# 42_PP1_NC.net
KiCad netlist of a schematic drawn in Altium Designer
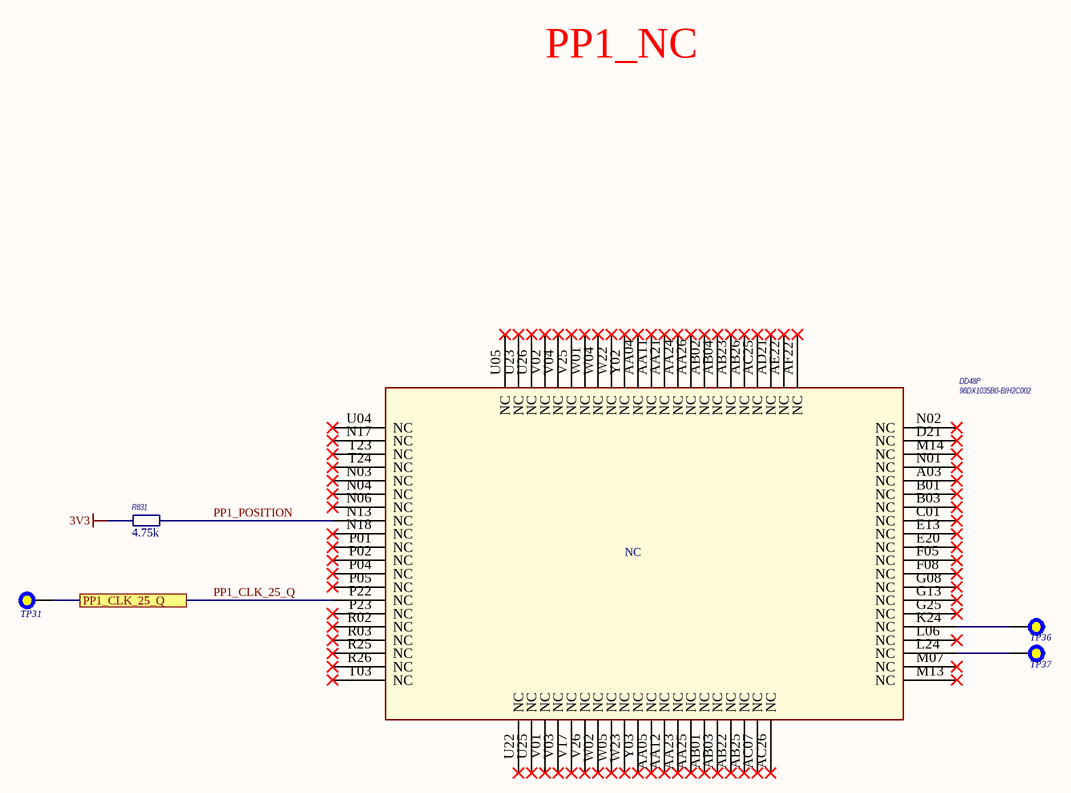
[diagram p0: 42_PP1_NC.SchDoc]

(export (version "E")
  (design (tool "Eeschema 10.0.6"))
  (components
    (comp (ref "DD48")
      (value "98DX1035B0-BIH2C002")
      (footprint "HSBGA617_27X27_1MM")
      (description "IC 24-PORT FE  4-PORT 2.5GE L2 ENTRY-LEVEL, CPU")
      (fields
        (field (name "CUSTOMER PART NUMBER") "Микросхема, 98DX1035B0-BIH2C002, IC 24-PORT FE 4-PORT 2.5GE L2 ENTRY-LEVEL, HSBGA617SBGA617")
        (field (name "MANUFACTURER") "Marvell Technology Group")
      )
      (libsource (lib "DIGITAL and ANALIG ICs") (part "98DX1035A1-BIH2C002"))
    )
    (comp (ref "R831")
      (value "ERJ-2RKF4751X")
      (footprint "R0402_IPC High Density")
      (description "R0402, 4.75k 1%")
      (fields
        (field (name "TOLERANCE") "±1%")
        (field (name "MANUFACTURER") "Panasonic")
        (field (name "RESISTANCE (OHMS)") "4.75k")
      )
      (libsource (lib "RESISTOR") (part "ERJ-2RKF4751X"))
    )
    (comp (ref "TP31")
      (value "Test Point 0.5mm pad")
      (footprint "Test Point 0.5mm")
      (libsource (lib "CONNECTORS") (part "Test Point 0.5mm pad"))
    )
    (comp (ref "TP36")
      (value "Test Point 0.5mm pad")
      (footprint "Test Point 0.5mm")
      (libsource (lib "CONNECTORS") (part "Test Point 0.5mm pad"))
    )
    (comp (ref "TP37")
      (value "Test Point 0.5mm pad")
      (footprint "Test Point 0.5mm")
      (libsource (lib "CONNECTORS") (part "Test Point 0.5mm pad"))
    )
  )
  (nets
    (net (code "1") (name "/PP1_CLK_25_Q") (class "Default")
      (node (ref "DD48") (pin "P22") (pinfunction "NC_P22") (pintype "power_in"))
      (node (ref "TP31") (pin "1") (pinfunction "1_1") (pintype "passive"))
    )
    (net (code "2") (name "/PP1_POSITION") (class "Default")
      (node (ref "DD48") (pin "N13") (pinfunction "NC_N13") (pintype "power_in"))
      (node (ref "R831") (pin "2") (pintype "passive"))
    )
    (net (code "3") (name "3V3") (class "Default") (node (ref "R831") (pin "1") (pintype "passive")))
    (net (code "4") (name "Net-(DD48P-NC-PadK24)") (class "Default")
      (node (ref "DD48") (pin "K24") (pinfunction "NC_K24") (pintype "power_in"))
      (node (ref "TP36") (pin "1") (pinfunction "1_1") (pintype "passive"))
    )
    (net (code "5") (name "Net-(DD48P-NC-PadL24)") (class "Default")
      (node (ref "DD48") (pin "L24") (pinfunction "NC_L24") (pintype "power_in"))
      (node (ref "TP37") (pin "1") (pinfunction "1_1") (pintype "passive"))
    )
    (net (code "6") (name "unconnected-(DD48P-NC-PadA03)") (class "Default")
      (node (ref "DD48") (pin "A03") (pinfunction "NC_A03") (pintype "power_in+no_connect"))
    )
    (net (code "7") (name "unconnected-(DD48P-NC-PadAA04)") (class "Default")
      (node (ref "DD48") (pin "AA04") (pinfunction "NC_AA04") (pintype "power_in+no_connect"))
    )
    (net (code "8") (name "unconnected-(DD48P-NC-PadAA05)") (class "Default")
      (node (ref "DD48") (pin "AA05") (pinfunction "NC_AA05") (pintype "power_in+no_connect"))
    )
    (net (code "9") (name "unconnected-(DD48P-NC-PadAA11)") (class "Default")
      (node (ref "DD48") (pin "AA11") (pinfunction "NC_AA11") (pintype "power_in+no_connect"))
    )
    (net (code "10") (name "unconnected-(DD48P-NC-PadAA12)") (class "Default")
      (node (ref "DD48") (pin "AA12") (pinfunction "NC_AA12") (pintype "power_in+no_connect"))
    )
    (net (code "11") (name "unconnected-(DD48P-NC-PadAA21)") (class "Default")
      (node (ref "DD48") (pin "AA21") (pinfunction "NC_AA21") (pintype "power_in+no_connect"))
    )
    (net (code "12") (name "unconnected-(DD48P-NC-PadAA23)") (class "Default")
      (node (ref "DD48") (pin "AA23") (pinfunction "NC_AA23") (pintype "power_in+no_connect"))
    )
    (net (code "13") (name "unconnected-(DD48P-NC-PadAA24)") (class "Default")
      (node (ref "DD48") (pin "AA24") (pinfunction "NC_AA24") (pintype "power_in+no_connect"))
    )
    (net (code "14") (name "unconnected-(DD48P-NC-PadAA25)") (class "Default")
      (node (ref "DD48") (pin "AA25") (pinfunction "NC_AA25") (pintype "power_in+no_connect"))
    )
    (net (code "15") (name "unconnected-(DD48P-NC-PadAA26)") (class "Default")
      (node (ref "DD48") (pin "AA26") (pinfunction "NC_AA26") (pintype "power_in+no_connect"))
    )
    (net (code "16") (name "unconnected-(DD48P-NC-PadAB01)") (class "Default")
      (node (ref "DD48") (pin "AB01") (pinfunction "NC_AB01") (pintype "power_in+no_connect"))
    )
    (net (code "17") (name "unconnected-(DD48P-NC-PadAB02)") (class "Default")
      (node (ref "DD48") (pin "AB02") (pinfunction "NC_AB02") (pintype "power_in+no_connect"))
    )
    (net (code "18") (name "unconnected-(DD48P-NC-PadAB03)") (class "Default")
      (node (ref "DD48") (pin "AB03") (pinfunction "NC_AB03") (pintype "power_in+no_connect"))
    )
    (net (code "19") (name "unconnected-(DD48P-NC-PadAB04)") (class "Default")
      (node (ref "DD48") (pin "AB04") (pinfunction "NC_AB04") (pintype "power_in+no_connect"))
    )
    (net (code "20") (name "unconnected-(DD48P-NC-PadAB22)") (class "Default")
      (node (ref "DD48") (pin "AB22") (pinfunction "NC_AB22") (pintype "power_in+no_connect"))
    )
    (net (code "21") (name "unconnected-(DD48P-NC-PadAB23)") (class "Default")
      (node (ref "DD48") (pin "AB23") (pinfunction "NC_AB23") (pintype "power_in+no_connect"))
    )
    (net (code "22") (name "unconnected-(DD48P-NC-PadAB25)") (class "Default")
      (node (ref "DD48") (pin "AB25") (pinfunction "NC_AB25") (pintype "power_in+no_connect"))
    )
    (net (code "23") (name "unconnected-(DD48P-NC-PadAB26)") (class "Default")
      (node (ref "DD48") (pin "AB26") (pinfunction "NC_AB26") (pintype "power_in+no_connect"))
    )
    (net (code "24") (name "unconnected-(DD48P-NC-PadAC07)") (class "Default")
      (node (ref "DD48") (pin "AC07") (pinfunction "NC_AC07") (pintype "power_in+no_connect"))
    )
    (net (code "25") (name "unconnected-(DD48P-NC-PadAC25)") (class "Default")
      (node (ref "DD48") (pin "AC25") (pinfunction "NC_AC25") (pintype "power_in+no_connect"))
    )
    (net (code "26") (name "unconnected-(DD48P-NC-PadAC26)") (class "Default")
      (node (ref "DD48") (pin "AC26") (pinfunction "NC_AC26") (pintype "power_in+no_connect"))
    )
    (net (code "27") (name "unconnected-(DD48P-NC-PadAD21)") (class "Default")
      (node (ref "DD48") (pin "AD21") (pinfunction "NC_AD21") (pintype "power_in+no_connect"))
    )
    (net (code "28") (name "unconnected-(DD48P-NC-PadAE22)") (class "Default")
      (node (ref "DD48") (pin "AE22") (pinfunction "NC_AE22") (pintype "power_in+no_connect"))
    )
    (net (code "29") (name "unconnected-(DD48P-NC-PadAF22)") (class "Default")
      (node (ref "DD48") (pin "AF22") (pinfunction "NC_AF22") (pintype "power_in+no_connect"))
    )
    (net (code "30") (name "unconnected-(DD48P-NC-PadB01)") (class "Default")
      (node (ref "DD48") (pin "B01") (pinfunction "NC_B01") (pintype "power_in+no_connect"))
    )
    (net (code "31") (name "unconnected-(DD48P-NC-PadB03)") (class "Default")
      (node (ref "DD48") (pin "B03") (pinfunction "NC_B03") (pintype "power_in+no_connect"))
    )
    (net (code "32") (name "unconnected-(DD48P-NC-PadC01)") (class "Default")
      (node (ref "DD48") (pin "C01") (pinfunction "NC_C01") (pintype "power_in+no_connect"))
    )
    (net (code "33") (name "unconnected-(DD48P-NC-PadD21)") (class "Default")
      (node (ref "DD48") (pin "D21") (pinfunction "NC_D21") (pintype "power_in+no_connect"))
    )
    (net (code "34") (name "unconnected-(DD48P-NC-PadE13)") (class "Default")
      (node (ref "DD48") (pin "E13") (pinfunction "NC_E13") (pintype "power_in+no_connect"))
    )
    (net (code "35") (name "unconnected-(DD48P-NC-PadE20)") (class "Default")
      (node (ref "DD48") (pin "E20") (pinfunction "NC_E20") (pintype "power_in+no_connect"))
    )
    (net (code "36") (name "unconnected-(DD48P-NC-PadF05)") (class "Default")
      (node (ref "DD48") (pin "F05") (pinfunction "NC_F05") (pintype "power_in+no_connect"))
    )
    (net (code "37") (name "unconnected-(DD48P-NC-PadF08)") (class "Default")
      (node (ref "DD48") (pin "F08") (pinfunction "NC_F08") (pintype "power_in+no_connect"))
    )
    (net (code "38") (name "unconnected-(DD48P-NC-PadG08)") (class "Default")
      (node (ref "DD48") (pin "G08") (pinfunction "NC_G08") (pintype "power_in+no_connect"))
    )
    (net (code "39") (name "unconnected-(DD48P-NC-PadG13)") (class "Default")
      (node (ref "DD48") (pin "G13") (pinfunction "NC_G13") (pintype "power_in+no_connect"))
    )
    (net (code "40") (name "unconnected-(DD48P-NC-PadG25)") (class "Default")
      (node (ref "DD48") (pin "G25") (pinfunction "NC_G25") (pintype "power_in+no_connect"))
    )
    (net (code "41") (name "unconnected-(DD48P-NC-PadL06)") (class "Default")
      (node (ref "DD48") (pin "L06") (pinfunction "NC_L06") (pintype "power_in+no_connect"))
    )
    (net (code "42") (name "unconnected-(DD48P-NC-PadM07)") (class "Default")
      (node (ref "DD48") (pin "M07") (pinfunction "NC_M07") (pintype "power_in+no_connect"))
    )
    (net (code "43") (name "unconnected-(DD48P-NC-PadM13)") (class "Default")
      (node (ref "DD48") (pin "M13") (pinfunction "NC_M13") (pintype "power_in+no_connect"))
    )
    (net (code "44") (name "unconnected-(DD48P-NC-PadM14)") (class "Default")
      (node (ref "DD48") (pin "M14") (pinfunction "NC_M14") (pintype "power_in+no_connect"))
    )
    (net (code "45") (name "unconnected-(DD48P-NC-PadN01)") (class "Default")
      (node (ref "DD48") (pin "N01") (pinfunction "NC_N01") (pintype "power_in+no_connect"))
    )
    (net (code "46") (name "unconnected-(DD48P-NC-PadN02)") (class "Default")
      (node (ref "DD48") (pin "N02") (pinfunction "NC_N02") (pintype "power_in+no_connect"))
    )
    (net (code "47") (name "unconnected-(DD48P-NC-PadN03)") (class "Default")
      (node (ref "DD48") (pin "N03") (pinfunction "NC_N03") (pintype "power_in+no_connect"))
    )
    (net (code "48") (name "unconnected-(DD48P-NC-PadN04)") (class "Default")
      (node (ref "DD48") (pin "N04") (pinfunction "NC_N04") (pintype "power_in+no_connect"))
    )
    (net (code "49") (name "unconnected-(DD48P-NC-PadN06)") (class "Default")
      (node (ref "DD48") (pin "N06") (pinfunction "NC_N06") (pintype "power_in+no_connect"))
    )
    (net (code "50") (name "unconnected-(DD48P-NC-PadN17)") (class "Default")
      (node (ref "DD48") (pin "N17") (pinfunction "NC_N17") (pintype "power_in+no_connect"))
    )
    (net (code "51") (name "unconnected-(DD48P-NC-PadN18)") (class "Default")
      (node (ref "DD48") (pin "N18") (pinfunction "NC_N18") (pintype "power_in+no_connect"))
    )
    (net (code "52") (name "unconnected-(DD48P-NC-PadP01)") (class "Default")
      (node (ref "DD48") (pin "P01") (pinfunction "NC_P01") (pintype "power_in+no_connect"))
    )
    (net (code "53") (name "unconnected-(DD48P-NC-PadP02)") (class "Default")
      (node (ref "DD48") (pin "P02") (pinfunction "NC_P02") (pintype "power_in+no_connect"))
    )
    (net (code "54") (name "unconnected-(DD48P-NC-PadP04)") (class "Default")
      (node (ref "DD48") (pin "P04") (pinfunction "NC_P04") (pintype "power_in+no_connect"))
    )
    (net (code "55") (name "unconnected-(DD48P-NC-PadP05)") (class "Default")
      (node (ref "DD48") (pin "P05") (pinfunction "NC_P05") (pintype "power_in+no_connect"))
    )
    (net (code "56") (name "unconnected-(DD48P-NC-PadP23)") (class "Default")
      (node (ref "DD48") (pin "P23") (pinfunction "NC_P23") (pintype "power_in+no_connect"))
    )
    (net (code "57") (name "unconnected-(DD48P-NC-PadR02)") (class "Default")
      (node (ref "DD48") (pin "R02") (pinfunction "NC_R02") (pintype "power_in+no_connect"))
    )
    (net (code "58") (name "unconnected-(DD48P-NC-PadR03)") (class "Default")
      (node (ref "DD48") (pin "R03") (pinfunction "NC_R03") (pintype "power_in+no_connect"))
    )
    (net (code "59") (name "unconnected-(DD48P-NC-PadR25)") (class "Default")
      (node (ref "DD48") (pin "R25") (pinfunction "NC_R25") (pintype "power_in+no_connect"))
    )
    (net (code "60") (name "unconnected-(DD48P-NC-PadR26)") (class "Default")
      (node (ref "DD48") (pin "R26") (pinfunction "NC_R26") (pintype "power_in+no_connect"))
    )
    (net (code "61") (name "unconnected-(DD48P-NC-PadT03)") (class "Default")
      (node (ref "DD48") (pin "T03") (pinfunction "NC_T03") (pintype "power_in+no_connect"))
    )
    (net (code "62") (name "unconnected-(DD48P-NC-PadT23)") (class "Default")
      (node (ref "DD48") (pin "T23") (pinfunction "NC_T23") (pintype "power_in+no_connect"))
    )
    (net (code "63") (name "unconnected-(DD48P-NC-PadT24)") (class "Default")
      (node (ref "DD48") (pin "T24") (pinfunction "NC_T24") (pintype "power_in+no_connect"))
    )
    (net (code "64") (name "unconnected-(DD48P-NC-PadU04)") (class "Default")
      (node (ref "DD48") (pin "U04") (pinfunction "NC_U04") (pintype "power_in+no_connect"))
    )
    (net (code "65") (name "unconnected-(DD48P-NC-PadU05)") (class "Default")
      (node (ref "DD48") (pin "U05") (pinfunction "NC_U05") (pintype "power_in+no_connect"))
    )
    (net (code "66") (name "unconnected-(DD48P-NC-PadU22)") (class "Default")
      (node (ref "DD48") (pin "U22") (pinfunction "NC_U22") (pintype "power_in+no_connect"))
    )
    (net (code "67") (name "unconnected-(DD48P-NC-PadU23)") (class "Default")
      (node (ref "DD48") (pin "U23") (pinfunction "NC_U23") (pintype "power_in+no_connect"))
    )
    (net (code "68") (name "unconnected-(DD48P-NC-PadU25)") (class "Default")
      (node (ref "DD48") (pin "U25") (pinfunction "NC_U25") (pintype "power_in+no_connect"))
    )
    (net (code "69") (name "unconnected-(DD48P-NC-PadU26)") (class "Default")
      (node (ref "DD48") (pin "U26") (pinfunction "NC_U26") (pintype "power_in+no_connect"))
    )
    (net (code "70") (name "unconnected-(DD48P-NC-PadV01)") (class "Default")
      (node (ref "DD48") (pin "V01") (pinfunction "NC_V01") (pintype "power_in+no_connect"))
    )
    (net (code "71") (name "unconnected-(DD48P-NC-PadV02)") (class "Default")
      (node (ref "DD48") (pin "V02") (pinfunction "NC_V02") (pintype "power_in+no_connect"))
    )
    (net (code "72") (name "unconnected-(DD48P-NC-PadV03)") (class "Default")
      (node (ref "DD48") (pin "V03") (pinfunction "NC_V03") (pintype "power_in+no_connect"))
    )
    (net (code "73") (name "unconnected-(DD48P-NC-PadV04)") (class "Default")
      (node (ref "DD48") (pin "V04") (pinfunction "NC_V04") (pintype "power_in+no_connect"))
    )
    (net (code "74") (name "unconnected-(DD48P-NC-PadV17)") (class "Default")
      (node (ref "DD48") (pin "V17") (pinfunction "NC_V17") (pintype "power_in+no_connect"))
    )
    (net (code "75") (name "unconnected-(DD48P-NC-PadV25)") (class "Default")
      (node (ref "DD48") (pin "V25") (pinfunction "NC_V25") (pintype "power_in+no_connect"))
    )
    (net (code "76") (name "unconnected-(DD48P-NC-PadV26)") (class "Default")
      (node (ref "DD48") (pin "V26") (pinfunction "NC_V26") (pintype "power_in+no_connect"))
    )
    (net (code "77") (name "unconnected-(DD48P-NC-PadW01)") (class "Default")
      (node (ref "DD48") (pin "W01") (pinfunction "NC_W01") (pintype "power_in+no_connect"))
    )
    (net (code "78") (name "unconnected-(DD48P-NC-PadW02)") (class "Default")
      (node (ref "DD48") (pin "W02") (pinfunction "NC_W02") (pintype "power_in+no_connect"))
    )
    (net (code "79") (name "unconnected-(DD48P-NC-PadW04)") (class "Default")
      (node (ref "DD48") (pin "W04") (pinfunction "NC_W04") (pintype "power_in+no_connect"))
    )
    (net (code "80") (name "unconnected-(DD48P-NC-PadW05)") (class "Default")
      (node (ref "DD48") (pin "W05") (pinfunction "NC_W05") (pintype "power_in+no_connect"))
    )
    (net (code "81") (name "unconnected-(DD48P-NC-PadW22)") (class "Default")
      (node (ref "DD48") (pin "W22") (pinfunction "NC_W22") (pintype "power_in+no_connect"))
    )
    (net (code "82") (name "unconnected-(DD48P-NC-PadW23)") (class "Default")
      (node (ref "DD48") (pin "W23") (pinfunction "NC_W23") (pintype "power_in+no_connect"))
    )
    (net (code "83") (name "unconnected-(DD48P-NC-PadY02)") (class "Default")
      (node (ref "DD48") (pin "Y02") (pinfunction "NC_Y02") (pintype "power_in+no_connect"))
    )
    (net (code "84") (name "unconnected-(DD48P-NC-PadY03)") (class "Default")
      (node (ref "DD48") (pin "Y03") (pinfunction "NC_Y03") (pintype "power_in+no_connect"))
    )
  )
)
